# Netzteil_OPV.net
KiCad netlist of a schematic drawn in EAGLE
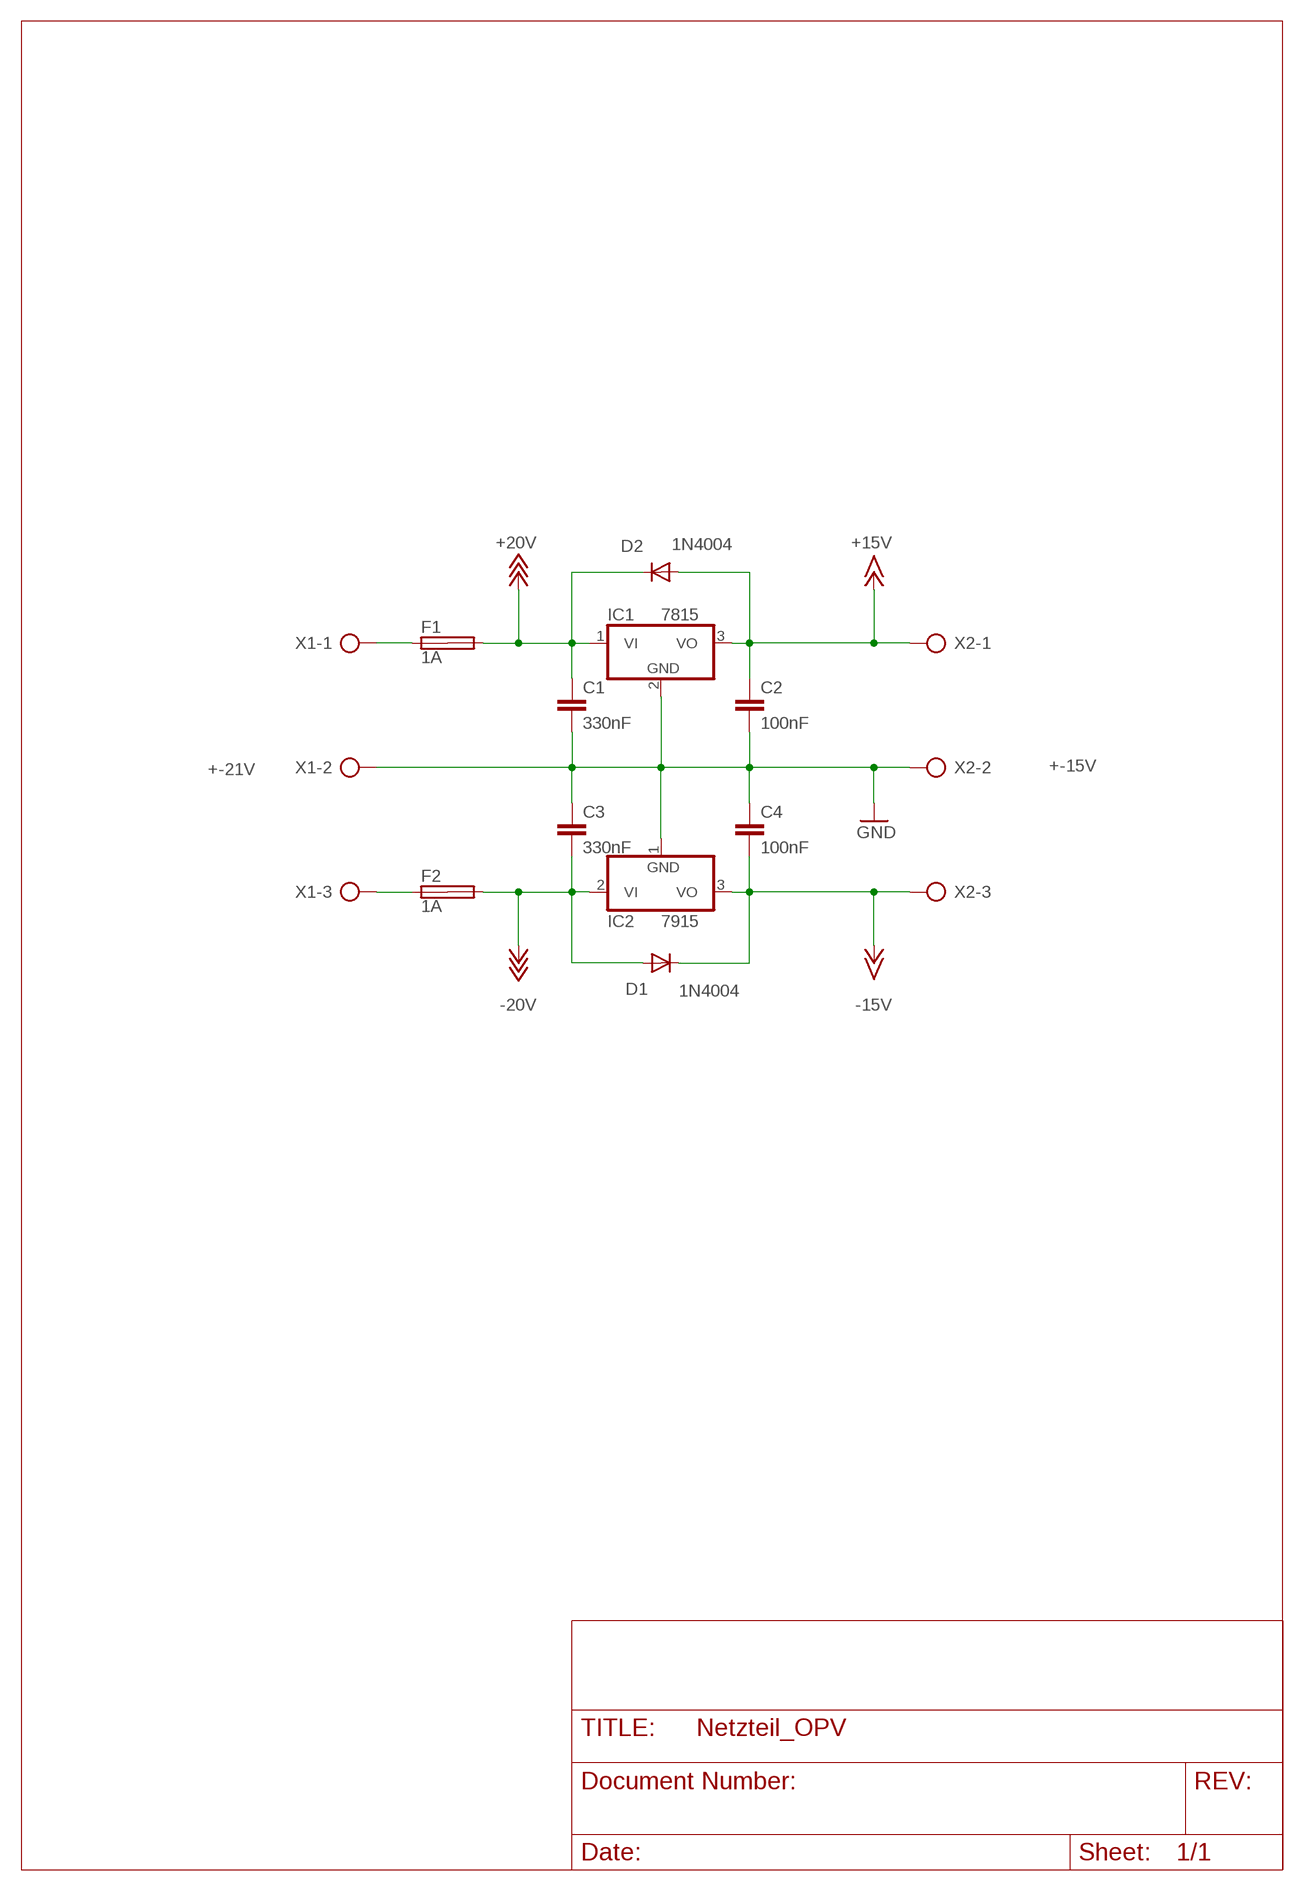
[diagram p0: schematic, sheet 1]

(export (version "E")
  (design (tool "Eeschema 10.0.6"))
  (components
    (comp (ref "C1")
      (value "330nF")
      (footprint "eagle-import:C025-025X050")
      (libsource (lib "eagle-import") (part "C-EU025-025X050"))
    )
    (comp (ref "C2")
      (value "100nF")
      (footprint "eagle-import:C025-025X050")
      (libsource (lib "eagle-import") (part "C-EU025-025X050"))
    )
    (comp (ref "C3")
      (value "330nF")
      (footprint "eagle-import:C025-025X050")
      (libsource (lib "eagle-import") (part "C-EU025-025X050"))
    )
    (comp (ref "C4")
      (value "100nF")
      (footprint "eagle-import:C025-025X050")
      (libsource (lib "eagle-import") (part "C-EU025-025X050"))
    )
    (comp (ref "D1")
      (value "1N4004")
      (footprint "eagle-import:DO41-10")
      (libsource (lib "eagle-import") (part "1N4004"))
    )
    (comp (ref "D2")
      (value "1N4004")
      (footprint "eagle-import:DO41-10")
      (libsource (lib "eagle-import") (part "1N4004"))
    )
    (comp (ref "F1")
      (value "1A")
      (footprint "eagle-import:SHK20L")
      (libsource (lib "eagle-import") (part "SHK20L"))
    )
    (comp (ref "F2")
      (value "1A")
      (footprint "eagle-import:SHK20L")
      (libsource (lib "eagle-import") (part "SHK20L"))
    )
    (comp (ref "IC1")
      (value "7815")
      (footprint "eagle-import:TO220H")
      (libsource (lib "eagle-import") (part "78T15"))
    )
    (comp (ref "IC2")
      (value "7915")
      (footprint "eagle-import:TO220H")
      (libsource (lib "eagle-import") (part "79T15"))
    )
    (comp (ref "X1")
      (value "+-21V")
      (footprint "eagle-import:AK300_3")
      (libsource (lib "eagle-import") (part "AK300/3"))
    )
    (comp (ref "X2")
      (value "+-15V")
      (footprint "eagle-import:AK300_3")
      (libsource (lib "eagle-import") (part "AK300/3"))
    )
  )
  (nets
    (net (code "1") (name "+15V") (class "Default")
      (node (ref "C2") (pin "1") (pinfunction "1_1") (pintype "passive"))
      (node (ref "D2") (pin "A") (pinfunction "A_A") (pintype "passive"))
      (node (ref "IC1") (pin "3") (pinfunction "VO_3") (pintype "passive"))
      (node (ref "X2") (pin "1") (pinfunction "KL_1") (pintype "passive"))
    )
    (net (code "2") (name "+20V") (class "Default")
      (node (ref "C1") (pin "1") (pinfunction "1_1") (pintype "passive"))
      (node (ref "D2") (pin "C") (pinfunction "C_C") (pintype "passive"))
      (node (ref "F1") (pin "2A") (pinfunction "2A_2A") (pintype "passive"))
      (node (ref "IC1") (pin "1") (pinfunction "VI_1") (pintype "input"))
    )
    (net (code "3") (name "-15V") (class "Default")
      (node (ref "C4") (pin "2") (pinfunction "2_2") (pintype "passive"))
      (node (ref "D1") (pin "C") (pinfunction "C_C") (pintype "passive"))
      (node (ref "IC2") (pin "3") (pinfunction "VO_3") (pintype "passive"))
      (node (ref "X2") (pin "3") (pinfunction "KL_3") (pintype "passive"))
    )
    (net (code "4") (name "-20V") (class "Default")
      (node (ref "C3") (pin "2") (pinfunction "2_2") (pintype "passive"))
      (node (ref "D1") (pin "A") (pinfunction "A_A") (pintype "passive"))
      (node (ref "F2") (pin "2A") (pinfunction "2A_2A") (pintype "passive"))
      (node (ref "IC2") (pin "2") (pinfunction "VI_2") (pintype "input"))
    )
    (net (code "5") (name "GND") (class "Default")
      (node (ref "C1") (pin "2") (pinfunction "2_2") (pintype "passive"))
      (node (ref "C2") (pin "2") (pinfunction "2_2") (pintype "passive"))
      (node (ref "C3") (pin "1") (pinfunction "1_1") (pintype "passive"))
      (node (ref "C4") (pin "1") (pinfunction "1_1") (pintype "passive"))
      (node (ref "IC1") (pin "2") (pinfunction "GND_2") (pintype "passive"))
      (node (ref "IC2") (pin "1") (pinfunction "GND_1") (pintype "passive"))
      (node (ref "X1") (pin "2") (pinfunction "KL_2") (pintype "passive"))
      (node (ref "X2") (pin "2") (pinfunction "KL_2") (pintype "passive"))
    )
    (net (code "6") (name "Net-(X1A-KL)") (class "Default")
      (node (ref "F1") (pin "1A") (pinfunction "1A_1A") (pintype "passive"))
      (node (ref "X1") (pin "1") (pinfunction "KL_1") (pintype "passive"))
    )
    (net (code "7") (name "Net-(X1C-KL)") (class "Default")
      (node (ref "F2") (pin "1A") (pinfunction "1A_1A") (pintype "passive"))
      (node (ref "X1") (pin "3") (pinfunction "KL_3") (pintype "passive"))
    )
    (net (code "8") (name "unconnected-(F1-Pad1B)") (class "Default")
      (node (ref "F1") (pin "1B") (pinfunction "1B_1B") (pintype "passive"))
    )
    (net (code "9") (name "unconnected-(F1-Pad2B)") (class "Default")
      (node (ref "F1") (pin "2B") (pinfunction "2B_2B") (pintype "passive"))
    )
    (net (code "10") (name "unconnected-(F2-Pad1B)") (class "Default")
      (node (ref "F2") (pin "1B") (pinfunction "1B_1B") (pintype "passive"))
    )
    (net (code "11") (name "unconnected-(F2-Pad2B)") (class "Default")
      (node (ref "F2") (pin "2B") (pinfunction "2B_2B") (pintype "passive"))
    )
  )
)
